# LCD_FRIDA.net
KiCad netlist of a schematic drawn in Altium Designer
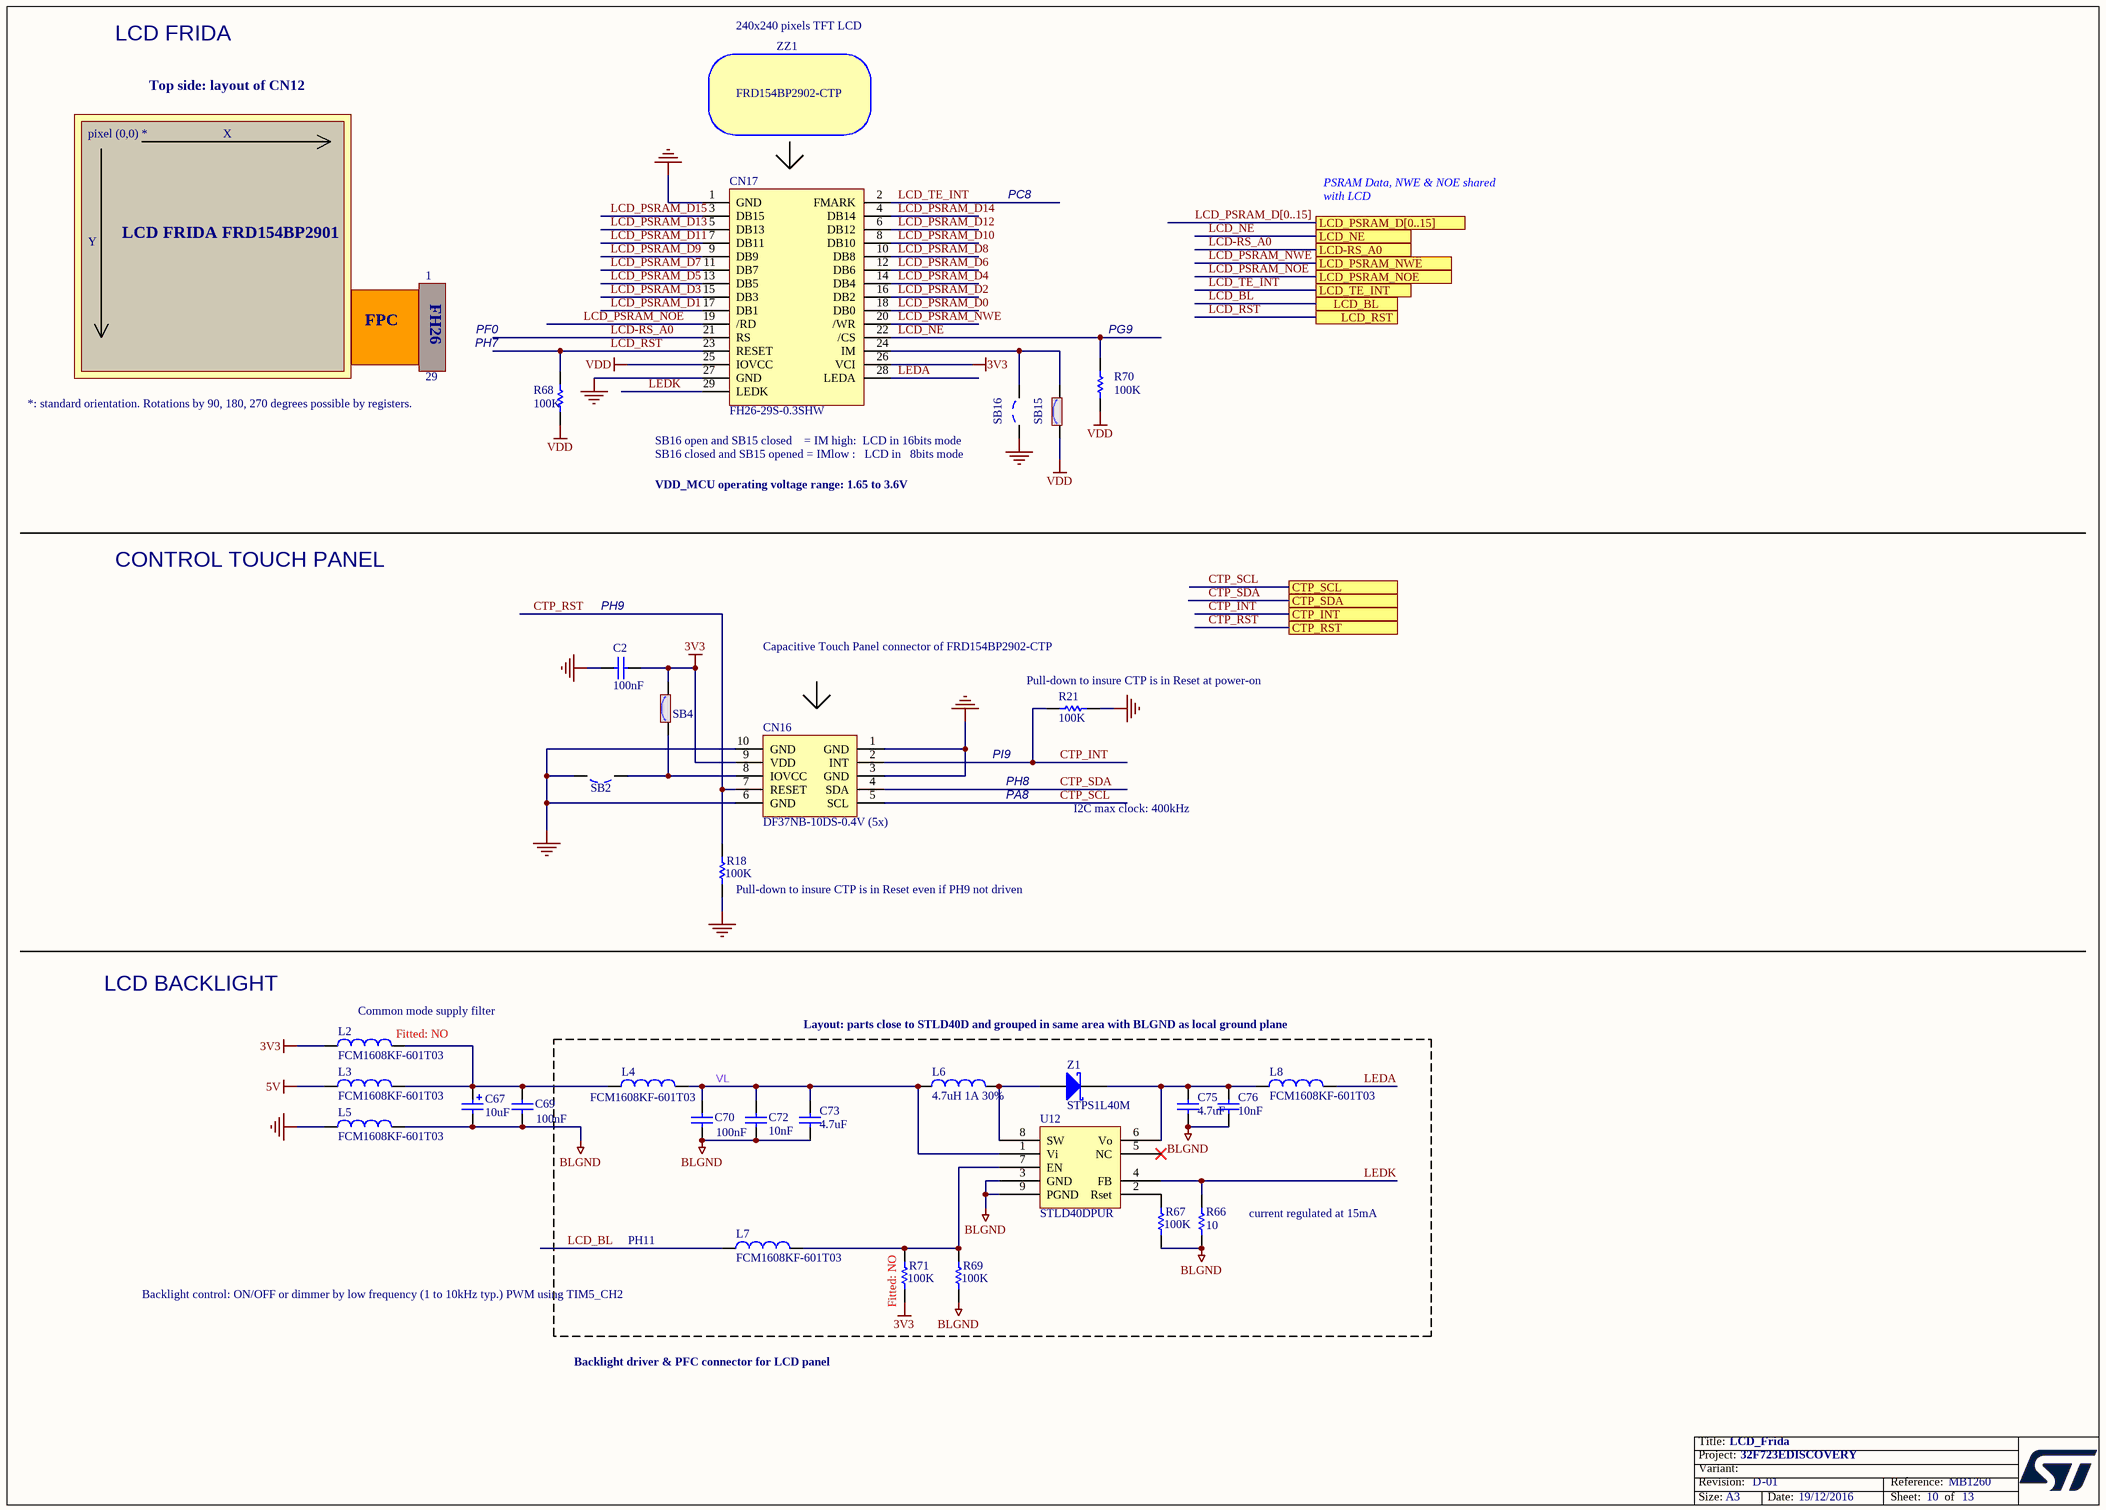
[diagram p0: LCD_FRIDA.SchDoc]

(export (version "E")
  (design (tool "Eeschema 10.0.6"))
  (components
    (comp (ref "C2")
      (value "100nF")
      (footprint "0402C")
      (description "Capacitor,100nF,16V,X7R,10%,0402,YAGEO")
      (libsource (lib "MCD_TOOLS") (part "Cap_100nF_X7R_10%_0402"))
    )
    (comp (ref "C67")
      (value "10uF")
      (footprint "TAN-A")
      (description "Polarized Capacitor,10uF,10V,10%,typeA,VISHAY")
      (fields (field (name "Comment") "10uF_POL_10%_TANA"))
      (libsource (lib "MCD_TOOLS_CAPACITOR") (part "Cap_10uF_POL_10%_TANA"))
    )
    (comp (ref "C69")
      (value "100nF")
      (footprint "0402C")
      (description "Capacitor,100nF,16V,X7R,10%,0402,YAGEO")
      (libsource (lib "MCD_TOOLS") (part "Cap_100nF_X7R_10%_0402"))
    )
    (comp (ref "C70")
      (value "100nF")
      (footprint "0402C")
      (description "Capacitor,100nF,16V,X7R,10%,0402,YAGEO")
      (libsource (lib "MCD_TOOLS") (part "Cap_100nF_X7R_10%_0402"))
    )
    (comp (ref "C72")
      (value "10nF")
      (footprint "0603C")
      (description "Capacitor,10nF,50V,X7R,10%,0603,YAGEO")
      (fields (field (name "Comment") "10nF_X7R_10%_0603"))
      (libsource (lib "MCD_TOOLS_CAPACITOR") (part "Cap_10nF_X7R_10%_0603"))
    )
    (comp (ref "C73")
      (value "4.7uF")
      (footprint "1206C")
      (description "Capacitor,4.7uF,50V, X7R,10%,1206,AVX")
      (fields (field (name "Comment") "4.7uF_X7R_10%_1206"))
      (libsource (lib "MCD_TOOLS_CAPACITOR") (part "Cap_4.7uF_X7R_10%_1206"))
    )
    (comp (ref "C75")
      (value "4.7uF")
      (footprint "1206C")
      (description "Capacitor,4.7uF,50V, X7R,10%,1206,AVX")
      (fields (field (name "Comment") "4.7uF_X7R_10%_1206"))
      (libsource (lib "MCD_TOOLS_CAPACITOR") (part "Cap_4.7uF_X7R_10%_1206"))
    )
    (comp (ref "C76")
      (value "10nF")
      (footprint "0603C")
      (description "Capacitor,10nF,50V,X7R,10%,0603,YAGEO")
      (fields (field (name "Comment") "10nF_X7R_10%_0603"))
      (libsource (lib "MCD_TOOLS_CAPACITOR") (part "Cap_10nF_X7R_10%_0603"))
    )
    (comp (ref "CN16")
      (value "DF37NB-10DS-0.4V (5x)")
      (footprint "DF37NB-10DS-0R4V")
      (description "Header, 5-Pin, Dual row")
      (fields (field (name "PUBLISHER") "Altium Limited"))
      (libsource (lib "MB1209") (part "Header 5X2A"))
    )
    (comp (ref "CN17")
      (value "FH26-29S-0.3SHW")
      (footprint "FH26-29S-0R3SHW")
      (description "29pins FPC connector")
      (libsource (lib "MCD_TEMP_NPA") (part "FH26-29S-0.3SHW"))
    )
    (comp (ref "L2")
      (value "FCM1608KF-601T03")
      (footprint "0603L")
      (description "Bead,600R,350mA,0603,FCM1608KF-601T03,Tai-tech")
      (fields (field (name "FITTED") "NO"))
      (libsource (lib "MCD_TOOLS_MISCELLANEOUS") (part "BEAD_600R_350MA_0603"))
    )
    (comp (ref "L3")
      (value "FCM1608KF-601T03")
      (footprint "0603L")
      (description "Bead,600R,350mA,0603,FCM1608KF-601T03,Tai-tech")
      (libsource (lib "MCD_TOOLS_MISCELLANEOUS") (part "BEAD_600R_350MA_0603"))
    )
    (comp (ref "L4")
      (value "FCM1608KF-601T03")
      (footprint "0603L")
      (description "Bead,600R,350mA,0603,FCM1608KF-601T03,Tai-tech")
      (libsource (lib "MCD_TOOLS_MISCELLANEOUS") (part "BEAD_600R_350MA_0603"))
    )
    (comp (ref "L5")
      (value "FCM1608KF-601T03")
      (footprint "0603L")
      (description "Bead,600R,350mA,0603,FCM1608KF-601T03,Tai-tech")
      (libsource (lib "MCD_TOOLS_MISCELLANEOUS") (part "BEAD_600R_350MA_0603"))
    )
    (comp (ref "L6")
      (value "4.7uH 1A 30%")
      (footprint "1210L")
      (description "FIXED IND 4.7UH 1A 180 MOHM 30% SMD")
      (libsource (lib "MCD_TOOLS_MISCELLANEOUS") (part "Ind_4.7uH_1A_30%"))
    )
    (comp (ref "L7")
      (value "FCM1608KF-601T03")
      (footprint "0603L")
      (description "Bead,600R,350mA,0603,FCM1608KF-601T03,Tai-tech")
      (libsource (lib "MCD_TOOLS_MISCELLANEOUS") (part "BEAD_600R_350MA_0603"))
    )
    (comp (ref "L8")
      (value "FCM1608KF-601T03")
      (footprint "0603L")
      (description "Bead,600R,350mA,0603,FCM1608KF-601T03,Tai-tech")
      (libsource (lib "MCD_TOOLS_MISCELLANEOUS") (part "BEAD_600R_350MA_0603"))
    )
    (comp (ref "R18")
      (value "100K")
      (footprint "0402R")
      (description "Resistor,100K,0402,1%,YAGEO")
      (fields (field (name "Comment") "100K_1%_0402"))
      (libsource (lib "MCD_TOOLS_RESISTOR") (part "Res_100K_1%_0402"))
    )
    (comp (ref "R21")
      (value "100K")
      (footprint "0402R")
      (description "Resistor,100K,0402,1%,YAGEO")
      (fields (field (name "Comment") "100K_1%_0402"))
      (libsource (lib "MCD_TOOLS_RESISTOR") (part "Res_100K_1%_0402"))
    )
    (comp (ref "R66")
      (value "10")
      (footprint "0603R")
      (description "Resistor,10,0603,1%,ROHM,1/4W")
      (fields (field (name "Comment") "10_1%_0603"))
      (libsource (lib "MCD_TOOLS_RESISTOR") (part "Res_10_1%_0603"))
    )
    (comp (ref "R67")
      (value "100K")
      (footprint "0402R")
      (description "Resistor,100K,0402,1%,YAGEO")
      (fields (field (name "Comment") "100K_1%_0402"))
      (libsource (lib "MCD_TOOLS_RESISTOR") (part "Res_100K_1%_0402"))
    )
    (comp (ref "R68")
      (value "100K")
      (footprint "0402R")
      (description "Resistor,100K,0402,1%,YAGEO")
      (fields (field (name "Comment") "100K_1%_0402"))
      (libsource (lib "MCD_TOOLS_RESISTOR") (part "Res_100K_1%_0402"))
    )
    (comp (ref "R69")
      (value "100K")
      (footprint "0402R")
      (description "Resistor,100K,0402,1%,YAGEO")
      (fields (field (name "Comment") "100K_1%_0402"))
      (libsource (lib "MCD_TOOLS_RESISTOR") (part "Res_100K_1%_0402"))
    )
    (comp (ref "R70")
      (value "100K")
      (footprint "0402R")
      (description "Resistor,100K,0402,1%,YAGEO")
      (fields (field (name "Comment") "100K_1%_0402"))
      (libsource (lib "MCD_TOOLS_RESISTOR") (part "Res_100K_1%_0402"))
    )
    (comp (ref "R71")
      (value "100K")
      (footprint "0402R")
      (description "Resistor,100K,0402,1%,YAGEO")
      (fields (field (name "FITTED") "NO") (field (name "Comment") "100K_1%_0402"))
      (libsource (lib "MCD_TOOLS_RESISTOR") (part "Res_100K_1%_0402"))
    )
    (comp (ref "SB2")
      (value "Solder Bridge OFF")
      (footprint "JP2_SMD")
      (libsource (lib "MCD_TOOLS") (part "SB_OFF"))
    )
    (comp (ref "SB4")
      (value "Solder Bridge ON")
      (footprint "JP2_SMD")
      (libsource (lib "MCD_TOOLS") (part "SB_ON"))
    )
    (comp (ref "SB15")
      (value "Solder Bridge ON")
      (footprint "JP2_SMD")
      (libsource (lib "MCD_TOOLS") (part "SB_ON"))
    )
    (comp (ref "SB16")
      (value "Solder Bridge OFF")
      (footprint "JP2_SMD")
      (libsource (lib "MCD_TOOLS") (part "SB_OFF"))
    )
    (comp (ref "U12")
      (value "STLD40DPUR")
      (footprint "SON8_0R65_3X3")
      (description "White LED power supply for large display backlight")
      (libsource (lib "MCD_TEMP_NPA") (part "STLD40DPMR"))
    )
    (comp (ref "Z1")
      (value "STPS1L40M")
      (footprint "DO-216AA")
      (description "Schottky Diode")
      (fields (field (name "PUBLISHER") "Altium Limited"))
      (libsource (lib "Miscellaneous Devices") (part "D Schottky"))
    )
    (comp (ref "ZZ1")
      (value "FRD154BP2902-CTP")
      (description "Frida LCD + Capacitive Touch Panel")
      (libsource (lib "Almos") (part "BoM_Item"))
    )
  )
  (nets
    (net (code "1") (name "/CTP_INT") (class "Default")
      (node (ref "CN16") (pin "2") (pinfunction "INT_2") (pintype "passive"))
      (node (ref "R21") (pin "2") (pinfunction "2_2") (pintype "passive"))
    )
    (net (code "2") (name "/CTP_RST") (class "Default")
      (node (ref "CN16") (pin "7") (pinfunction "RESET_7") (pintype "passive"))
      (node (ref "R18") (pin "2") (pinfunction "2_2") (pintype "passive"))
    )
    (net (code "3") (name "/CTP_SCL") (class "Default")
      (node (ref "CN16") (pin "5") (pinfunction "SCL_5") (pintype "passive"))
    )
    (net (code "4") (name "/CTP_SDA") (class "Default")
      (node (ref "CN16") (pin "4") (pinfunction "SDA_4") (pintype "passive"))
    )
    (net (code "5") (name "/LCD-RS_A0") (class "Default")
      (node (ref "CN17") (pin "21") (pinfunction "RS_21") (pintype "passive"))
    )
    (net (code "6") (name "/LCD_BL") (class "Default")
      (node (ref "L7") (pin "1") (pinfunction "1_1") (pintype "passive"))
    )
    (net (code "7") (name "/LCD_NE") (class "Default")
      (node (ref "CN17") (pin "22") (pinfunction "/CS_22") (pintype "passive"))
      (node (ref "R70") (pin "2") (pinfunction "2_2") (pintype "passive"))
    )
    (net (code "8") (name "/LCD_PSRAM_D0") (class "Default")
      (node (ref "CN17") (pin "18") (pinfunction "DB0_18") (pintype "passive"))
    )
    (net (code "9") (name "/LCD_PSRAM_D1") (class "Default")
      (node (ref "CN17") (pin "17") (pinfunction "DB1_17") (pintype "passive"))
    )
    (net (code "10") (name "/LCD_PSRAM_D2") (class "Default")
      (node (ref "CN17") (pin "16") (pinfunction "DB2_16") (pintype "passive"))
    )
    (net (code "11") (name "/LCD_PSRAM_D3") (class "Default")
      (node (ref "CN17") (pin "15") (pinfunction "DB3_15") (pintype "passive"))
    )
    (net (code "12") (name "/LCD_PSRAM_D4") (class "Default")
      (node (ref "CN17") (pin "14") (pinfunction "DB4_14") (pintype "passive"))
    )
    (net (code "13") (name "/LCD_PSRAM_D5") (class "Default")
      (node (ref "CN17") (pin "13") (pinfunction "DB5_13") (pintype "passive"))
    )
    (net (code "14") (name "/LCD_PSRAM_D6") (class "Default")
      (node (ref "CN17") (pin "12") (pinfunction "DB6_12") (pintype "passive"))
    )
    (net (code "15") (name "/LCD_PSRAM_D7") (class "Default")
      (node (ref "CN17") (pin "11") (pinfunction "DB7_11") (pintype "passive"))
    )
    (net (code "16") (name "/LCD_PSRAM_D8") (class "Default")
      (node (ref "CN17") (pin "10") (pinfunction "DB8_10") (pintype "passive"))
    )
    (net (code "17") (name "/LCD_PSRAM_D9") (class "Default")
      (node (ref "CN17") (pin "9") (pinfunction "DB9_9") (pintype "passive"))
    )
    (net (code "18") (name "/LCD_PSRAM_D10") (class "Default")
      (node (ref "CN17") (pin "8") (pinfunction "DB10_8") (pintype "passive"))
    )
    (net (code "19") (name "/LCD_PSRAM_D11") (class "Default")
      (node (ref "CN17") (pin "7") (pinfunction "DB11_7") (pintype "passive"))
    )
    (net (code "20") (name "/LCD_PSRAM_D12") (class "Default")
      (node (ref "CN17") (pin "6") (pinfunction "DB12_6") (pintype "passive"))
    )
    (net (code "21") (name "/LCD_PSRAM_D13") (class "Default")
      (node (ref "CN17") (pin "5") (pinfunction "DB13_5") (pintype "passive"))
    )
    (net (code "22") (name "/LCD_PSRAM_D14") (class "Default")
      (node (ref "CN17") (pin "4") (pinfunction "DB14_4") (pintype "passive"))
    )
    (net (code "23") (name "/LCD_PSRAM_D15") (class "Default")
      (node (ref "CN17") (pin "3") (pinfunction "DB15_3") (pintype "passive"))
    )
    (net (code "25") (name "/LCD_PSRAM_NOE") (class "Default")
      (node (ref "CN17") (pin "19") (pinfunction "/RD_19") (pintype "passive"))
    )
    (net (code "26") (name "/LCD_PSRAM_NWE") (class "Default")
      (node (ref "CN17") (pin "20") (pinfunction "/WR_20") (pintype "passive"))
    )
    (net (code "27") (name "/LCD_RST") (class "Default")
      (node (ref "CN17") (pin "23") (pinfunction "RESET_23") (pintype "passive"))
      (node (ref "R68") (pin "2") (pinfunction "2_2") (pintype "passive"))
    )
    (net (code "28") (name "/LCD_TE_INT") (class "Default")
      (node (ref "CN17") (pin "2") (pinfunction "FMARK_2") (pintype "passive"))
    )
    (net (code "29") (name "/LEDA") (class "Default")
      (node (ref "CN17") (pin "28") (pinfunction "LEDA_28") (pintype "passive"))
      (node (ref "L8") (pin "2") (pinfunction "2_2") (pintype "passive"))
    )
    (net (code "30") (name "/LEDK") (class "Default")
      (node (ref "CN17") (pin "29") (pinfunction "LEDK_29") (pintype "passive"))
      (node (ref "R66") (pin "2") (pinfunction "2_2") (pintype "passive"))
      (node (ref "U12") (pin "4") (pinfunction "FB_4") (pintype "passive"))
    )
    (net (code "31") (name "/VL") (class "Default")
      (node (ref "C70") (pin "2") (pinfunction "2_2") (pintype "passive"))
      (node (ref "C72") (pin "2") (pinfunction "2_2") (pintype "passive"))
      (node (ref "C73") (pin "2") (pinfunction "2_2") (pintype "passive"))
      (node (ref "L4") (pin "2") (pinfunction "2_2") (pintype "passive"))
      (node (ref "L6") (pin "1") (pinfunction "1_1") (pintype "passive"))
      (node (ref "U12") (pin "1") (pinfunction "Vi_1") (pintype "passive"))
    )
    (net (code "32") (name "3V3") (class "Default")
      (node (ref "C2") (pin "1") (pinfunction "1_1") (pintype "passive"))
      (node (ref "CN16") (pin "9") (pinfunction "VDD_9") (pintype "passive"))
      (node (ref "CN17") (pin "26") (pinfunction "VCI_26") (pintype "passive"))
      (node (ref "L2") (pin "1") (pinfunction "1_1") (pintype "passive"))
      (node (ref "R71") (pin "1") (pinfunction "1_1") (pintype "passive"))
      (node (ref "SB4") (pin "2") (pinfunction "2_2") (pintype "passive"))
    )
    (net (code "33") (name "5V") (class "Default")
      (node (ref "L3") (pin "1") (pinfunction "1_1") (pintype "passive"))
    )
    (net (code "34") (name "BLGND") (class "Default")
      (node (ref "C67") (pin "2") (pinfunction "2_2") (pintype "passive"))
      (node (ref "C69") (pin "1") (pinfunction "1_1") (pintype "passive"))
      (node (ref "C70") (pin "1") (pinfunction "1_1") (pintype "passive"))
      (node (ref "C72") (pin "1") (pinfunction "1_1") (pintype "passive"))
      (node (ref "C73") (pin "1") (pinfunction "1_1") (pintype "passive"))
      (node (ref "C75") (pin "1") (pinfunction "1_1") (pintype "passive"))
      (node (ref "C76") (pin "1") (pinfunction "1_1") (pintype "passive"))
      (node (ref "L5") (pin "2") (pinfunction "2_2") (pintype "passive"))
      (node (ref "R66") (pin "1") (pinfunction "1_1") (pintype "passive"))
      (node (ref "R67") (pin "1") (pinfunction "1_1") (pintype "passive"))
      (node (ref "R69") (pin "1") (pinfunction "1_1") (pintype "passive"))
      (node (ref "U12") (pin "3") (pinfunction "GND_3") (pintype "passive"))
      (node (ref "U12") (pin "9") (pinfunction "PGND_9") (pintype "passive"))
    )
    (net (code "35") (name "GND") (class "Default")
      (node (ref "C2") (pin "2") (pinfunction "2_2") (pintype "passive"))
      (node (ref "CN16") (pin "1") (pinfunction "GND_1") (pintype "passive"))
      (node (ref "CN16") (pin "10") (pinfunction "GND_10") (pintype "passive"))
      (node (ref "CN16") (pin "3") (pinfunction "GND_3") (pintype "passive"))
      (node (ref "CN16") (pin "6") (pinfunction "GND_6") (pintype "passive"))
      (node (ref "CN17") (pin "1") (pinfunction "GND_1") (pintype "passive"))
      (node (ref "CN17") (pin "27") (pinfunction "GND_27") (pintype "passive"))
      (node (ref "L5") (pin "1") (pinfunction "1_1") (pintype "passive"))
      (node (ref "R18") (pin "1") (pinfunction "1_1") (pintype "passive"))
      (node (ref "R21") (pin "1") (pinfunction "1_1") (pintype "passive"))
      (node (ref "SB16") (pin "1") (pinfunction "1_1") (pintype "passive"))
      (node (ref "SB2") (pin "2") (pinfunction "2_2") (pintype "passive"))
    )
    (net (code "36") (name "Net-(C67-Pad1)") (class "Default")
      (node (ref "C67") (pin "1") (pinfunction "1_1") (pintype "passive"))
      (node (ref "C69") (pin "2") (pinfunction "2_2") (pintype "passive"))
      (node (ref "L2") (pin "2") (pinfunction "2_2") (pintype "passive"))
      (node (ref "L3") (pin "2") (pinfunction "2_2") (pintype "passive"))
      (node (ref "L4") (pin "1") (pinfunction "1_1") (pintype "passive"))
    )
    (net (code "37") (name "Net-(CN16-IOVCC)") (class "Default")
      (node (ref "CN16") (pin "8") (pinfunction "IOVCC_8") (pintype "passive"))
      (node (ref "SB2") (pin "1") (pinfunction "1_1") (pintype "passive"))
      (node (ref "SB4") (pin "1") (pinfunction "1_1") (pintype "passive"))
    )
    (net (code "38") (name "Net-(CN17-IM)") (class "Default")
      (node (ref "CN17") (pin "24") (pinfunction "IM_24") (pintype "passive"))
      (node (ref "SB15") (pin "2") (pinfunction "2_2") (pintype "passive"))
      (node (ref "SB16") (pin "2") (pinfunction "2_2") (pintype "passive"))
    )
    (net (code "39") (name "Net-(U12-EN)") (class "Default")
      (node (ref "L7") (pin "2") (pinfunction "2_2") (pintype "passive"))
      (node (ref "R69") (pin "2") (pinfunction "2_2") (pintype "passive"))
      (node (ref "R71") (pin "2") (pinfunction "2_2") (pintype "passive"))
      (node (ref "U12") (pin "7") (pinfunction "EN_7") (pintype "passive"))
    )
    (net (code "40") (name "Net-(U12-Rset)") (class "Default")
      (node (ref "R67") (pin "2") (pinfunction "2_2") (pintype "passive"))
      (node (ref "U12") (pin "2") (pinfunction "Rset_2") (pintype "passive"))
    )
    (net (code "41") (name "Net-(U12-SW)") (class "Default")
      (node (ref "L6") (pin "2") (pinfunction "2_2") (pintype "passive"))
      (node (ref "U12") (pin "8") (pinfunction "SW_8") (pintype "passive"))
      (node (ref "Z1") (pin "1") (pinfunction "A_1") (pintype "passive"))
    )
    (net (code "42") (name "Net-(U12-Vo)") (class "Default")
      (node (ref "C75") (pin "2") (pinfunction "2_2") (pintype "passive"))
      (node (ref "C76") (pin "2") (pinfunction "2_2") (pintype "passive"))
      (node (ref "L8") (pin "1") (pinfunction "1_1") (pintype "passive"))
      (node (ref "U12") (pin "6") (pinfunction "Vo_6") (pintype "passive"))
      (node (ref "Z1") (pin "2") (pinfunction "K_2") (pintype "passive"))
    )
    (net (code "43") (name "VDD") (class "Default")
      (node (ref "CN17") (pin "25") (pinfunction "IOVCC_25") (pintype "passive"))
      (node (ref "R68") (pin "1") (pinfunction "1_1") (pintype "passive"))
      (node (ref "R70") (pin "1") (pinfunction "1_1") (pintype "passive"))
      (node (ref "SB15") (pin "1") (pinfunction "1_1") (pintype "passive"))
    )
    (net (code "44") (name "unconnected-(U12-NC-Pad5)") (class "Default")
      (node (ref "U12") (pin "5") (pinfunction "NC_5") (pintype "passive+no_connect"))
    )
  )
)
